# whte_noise.net
KiCad netlist of a schematic drawn in Altium Designer
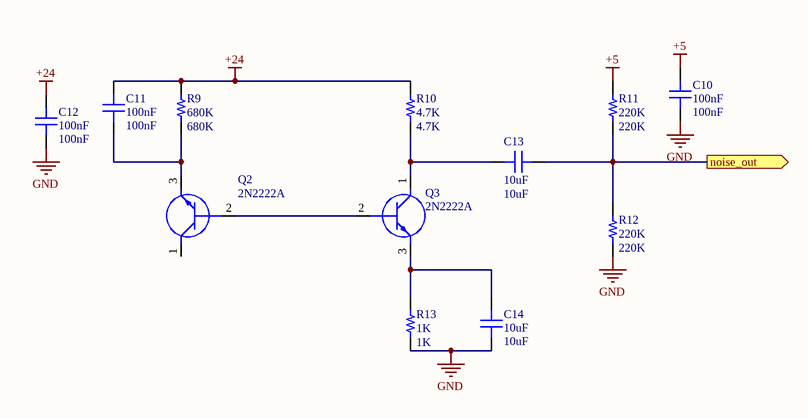
[diagram p0: whte_noise.SchDoc]

(export (version "E")
  (design (tool "Eeschema 10.0.6"))
  (components
    (comp (ref "C10")
      (value "100nF")
      (footprint "cap805")
      (description "CAP SMD 0805")
      (fields (field (name "PART NUMBER") "C0805X106K9RAC7800") (field (name "ALTIUM_VALUE") "100nF"))
      (libsource (lib "lamp control-ver2") (part "Capacitor"))
    )
    (comp (ref "C11")
      (value "100nF")
      (footprint "cap805")
      (description "CAP SMD 0805")
      (fields (field (name "PART NUMBER") "C0805X106K9RAC7800") (field (name "ALTIUM_VALUE") "100nF"))
      (libsource (lib "lamp control-ver2") (part "Capacitor"))
    )
    (comp (ref "C12")
      (value "100nF")
      (footprint "cap805")
      (description "CAP SMD 0805")
      (fields (field (name "PART NUMBER") "C0805X106K9RAC7800") (field (name "ALTIUM_VALUE") "100nF"))
      (libsource (lib "lamp control-ver2") (part "Capacitor"))
    )
    (comp (ref "C13")
      (value "10uF")
      (footprint "cap805")
      (description "CAP SMD 0805")
      (fields (field (name "PART NUMBER") "C0805X106K9RAC7800") (field (name "ALTIUM_VALUE") "10uF"))
      (libsource (lib "lamp control-ver2") (part "Capacitor"))
    )
    (comp (ref "C14")
      (value "10uF")
      (footprint "cap805")
      (description "CAP SMD 0805")
      (fields (field (name "PART NUMBER") "C0805X106K9RAC7800") (field (name "ALTIUM_VALUE") "10uF"))
      (libsource (lib "lamp control-ver2") (part "Capacitor"))
    )
    (comp (ref "Q2")
      (value "2N2222A")
      (footprint "soT95p280x130-3n")
      (description "Transistor BJT NPN SMD")
      (libsource (lib "*") (part "2N2222A"))
    )
    (comp (ref "Q3")
      (value "2N2222A")
      (footprint "soT95p280x130-3n")
      (description "Transistor BJT NPN SMD")
      (libsource (lib "*") (part "2N2222A"))
    )
    (comp (ref "R9")
      (value "680K")
      (footprint "0603R")
      (description "RES SMD 0603")
      (fields (field (name "PART NUMBER") "RCS0805100KFKEA") (field (name "ALTIUM_VALUE") "680K"))
      (libsource (lib "lamp control-ver2") (part "Resistor"))
    )
    (comp (ref "R10")
      (value "4.7K")
      (footprint "0603R")
      (description "RES SMD 0603")
      (fields (field (name "PART NUMBER") "RCS0805100KFKEA") (field (name "ALTIUM_VALUE") "4.7K"))
      (libsource (lib "lamp control-ver2") (part "Resistor"))
    )
    (comp (ref "R11")
      (value "220K")
      (footprint "0603R")
      (description "RES SMD 0603")
      (fields (field (name "PART NUMBER") "RCS0805100KFKEA") (field (name "ALTIUM_VALUE") "220K"))
      (libsource (lib "lamp control-ver2") (part "Resistor"))
    )
    (comp (ref "R12")
      (value "220K")
      (footprint "0603R")
      (description "RES SMD 0603")
      (fields (field (name "PART NUMBER") "RCS0805100KFKEA") (field (name "ALTIUM_VALUE") "220K"))
      (libsource (lib "lamp control-ver2") (part "Resistor"))
    )
    (comp (ref "R13")
      (value "1K")
      (footprint "0603R")
      (description "RES SMD 0603")
      (fields (field (name "PART NUMBER") "RCS0805100KFKEA") (field (name "ALTIUM_VALUE") "1K"))
      (libsource (lib "lamp control-ver2") (part "Resistor"))
    )
  )
  (nets
    (net (code "1") (name "+5") (class "Default")
      (node (ref "C10") (pin "1") (pinfunction "1_1") (pintype "passive"))
      (node (ref "R11") (pin "2") (pinfunction "2_2") (pintype "passive"))
    )
    (net (code "2") (name "+24") (class "Default")
      (node (ref "C11") (pin "2") (pinfunction "2_2") (pintype "passive"))
      (node (ref "C12") (pin "1") (pinfunction "1_1") (pintype "passive"))
      (node (ref "R10") (pin "2") (pinfunction "2_2") (pintype "passive"))
      (node (ref "R9") (pin "2") (pinfunction "2_2") (pintype "passive"))
    )
    (net (code "3") (name "/noise_out") (class "Default")
      (node (ref "C13") (pin "1") (pinfunction "1_1") (pintype "passive"))
      (node (ref "R11") (pin "1") (pinfunction "1_1") (pintype "passive"))
      (node (ref "R12") (pin "2") (pinfunction "2_2") (pintype "passive"))
    )
    (net (code "4") (name "GND") (class "Default")
      (node (ref "C10") (pin "2") (pinfunction "2_2") (pintype "passive"))
      (node (ref "C12") (pin "2") (pinfunction "2_2") (pintype "passive"))
      (node (ref "C14") (pin "1") (pinfunction "1_1") (pintype "passive"))
      (node (ref "R12") (pin "1") (pinfunction "1_1") (pintype "passive"))
      (node (ref "R13") (pin "1") (pinfunction "1_1") (pintype "passive"))
    )
    (net (code "5") (name "Net-(Q2-B)") (class "Default")
      (node (ref "Q2") (pin "2") (pinfunction "B_2") (pintype "passive"))
      (node (ref "Q3") (pin "2") (pinfunction "B_2") (pintype "passive"))
    )
    (net (code "6") (name "Net-(Q2-E)") (class "Default")
      (node (ref "C11") (pin "1") (pinfunction "1_1") (pintype "passive"))
      (node (ref "Q2") (pin "3") (pinfunction "E_3") (pintype "passive"))
      (node (ref "R9") (pin "1") (pinfunction "1_1") (pintype "passive"))
    )
    (net (code "7") (name "Net-(Q3-C)") (class "Default")
      (node (ref "C13") (pin "2") (pinfunction "2_2") (pintype "passive"))
      (node (ref "Q3") (pin "1") (pinfunction "C_1") (pintype "passive"))
      (node (ref "R10") (pin "1") (pinfunction "1_1") (pintype "passive"))
    )
    (net (code "8") (name "Net-(Q3-E)") (class "Default")
      (node (ref "C14") (pin "2") (pinfunction "2_2") (pintype "passive"))
      (node (ref "Q3") (pin "3") (pinfunction "E_3") (pintype "passive"))
      (node (ref "R13") (pin "2") (pinfunction "2_2") (pintype "passive"))
    )
    (net (code "9") (name "unconnected-(Q2-C-Pad1)") (class "Default")
      (node (ref "Q2") (pin "1") (pinfunction "C_1") (pintype "passive"))
    )
  )
)
